# VESC6_4.net
KiCad netlist of a schematic drawn in Altium Designer
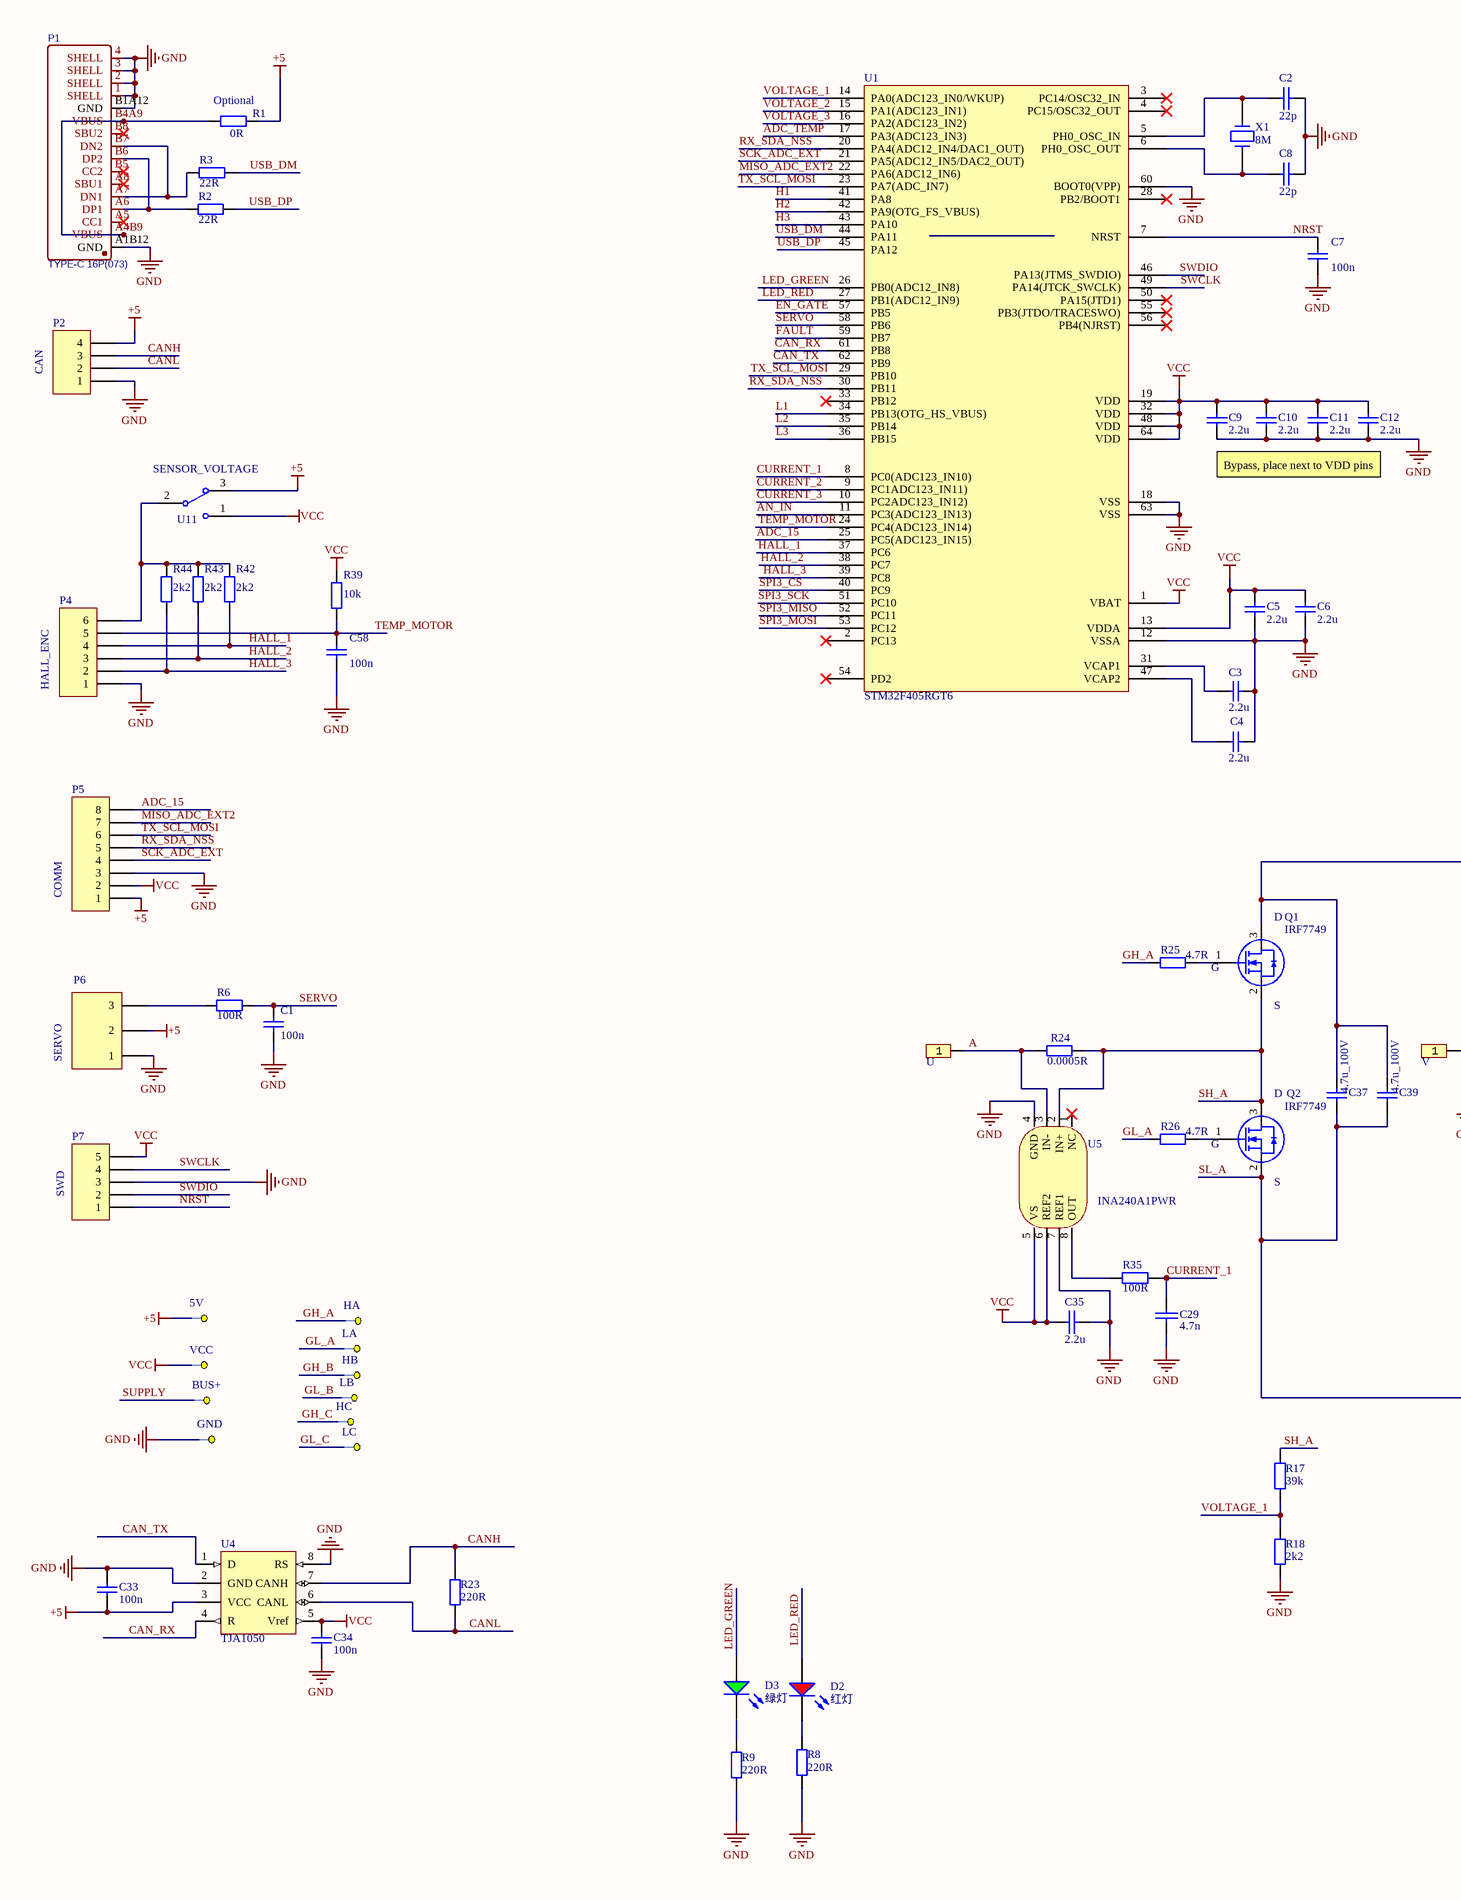
[diagram p0: VESC6.4.SchDoc, left]
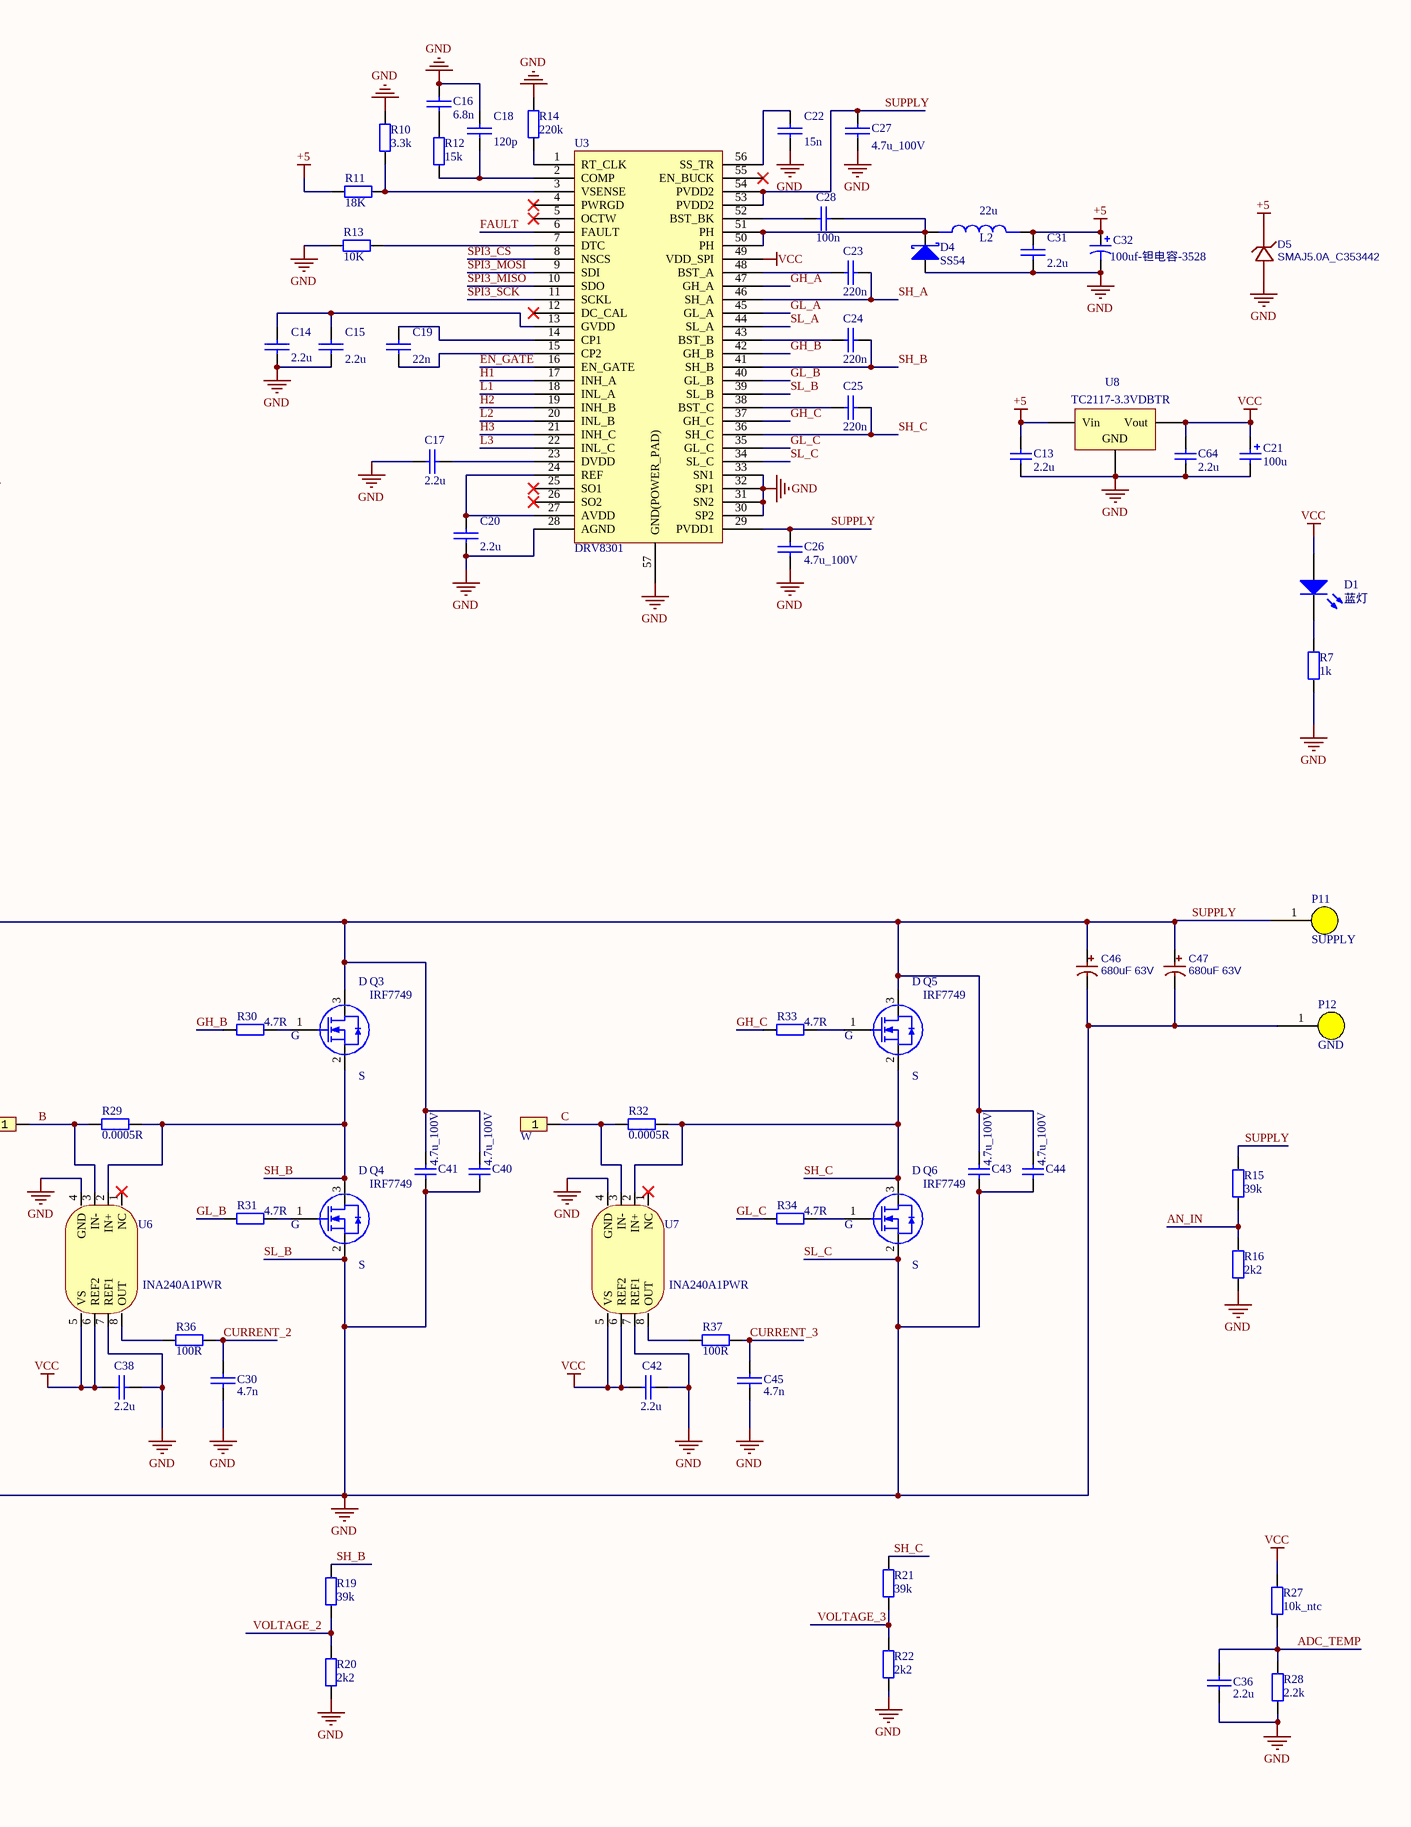
[diagram p1: VESC6.4.SchDoc, right]

(export (version "E")
  (design (tool "Eeschema 10.0.6"))
  (components
    (comp (ref "5V")
      (value "TEST")
      (footprint "TEST_2mm")
      (description "测试点")
      (libsource (lib "其它") (part "TEST"))
    )
    (comp (ref "BUS+")
      (value "TEST")
      (footprint "TEST_2mm")
      (description "测试点")
      (libsource (lib "其它") (part "TEST"))
    )
    (comp (ref "C1")
      (value "100n")
      (footprint "0603_C")
      (description "贴片电容")
      (libsource (lib "VESC_6") (part "0603 100nF (104) 10% 50V"))
    )
    (comp (ref "C2")
      (value "22p")
      (footprint "0603_C")
      (description "贴片电容")
      (libsource (lib "MY SCH LIB") (part "CAP"))
    )
    (comp (ref "C3")
      (value "2.2u")
      (footprint "0603_C")
      (description "贴片电容")
      (libsource (lib "VESC_6") (part "0603 2.2uF (225) 10% 16V"))
    )
    (comp (ref "C4")
      (value "2.2u")
      (footprint "0603_C")
      (description "贴片电容")
      (libsource (lib "VESC_6") (part "0603 2.2uF (225) 10% 16V"))
    )
    (comp (ref "C5")
      (value "2.2u")
      (footprint "0603_C")
      (description "贴片电容")
      (libsource (lib "VESC_6") (part "0603 2.2uF (225) 10% 16V"))
    )
    (comp (ref "C6")
      (value "2.2u")
      (footprint "0603_C")
      (description "贴片电容")
      (libsource (lib "VESC_6") (part "0603 2.2uF (225) 10% 16V"))
    )
    (comp (ref "C7")
      (value "100n")
      (footprint "0603_C")
      (description "贴片电容")
      (libsource (lib "VESC_6") (part "0603 100nF (104) 10% 50V"))
    )
    (comp (ref "C8")
      (value "22p")
      (footprint "0603_C")
      (description "贴片电容")
      (libsource (lib "MY SCH LIB") (part "CAP"))
    )
    (comp (ref "C9")
      (value "2.2u")
      (footprint "0603_C")
      (description "贴片电容")
      (libsource (lib "VESC_6") (part "0603 2.2uF (225) 10% 16V"))
    )
    (comp (ref "C10")
      (value "2.2u")
      (footprint "0603_C")
      (description "贴片电容")
      (libsource (lib "VESC_6") (part "0603 2.2uF (225) 10% 16V"))
    )
    (comp (ref "C11")
      (value "2.2u")
      (footprint "0603_C")
      (description "贴片电容")
      (libsource (lib "VESC_6") (part "0603 2.2uF (225) 10% 16V"))
    )
    (comp (ref "C12")
      (value "2.2u")
      (footprint "0603_C")
      (description "贴片电容")
      (libsource (lib "VESC_6") (part "0603 2.2uF (225) 10% 16V"))
    )
    (comp (ref "C13")
      (value "2.2u")
      (footprint "0603_C")
      (description "贴片电容")
      (libsource (lib "Miscellaneous Devices LC") (part "0603 2.2uF (225) 10% 16V"))
    )
    (comp (ref "C14") (value "2.2u") (footprint "0603_C") (libsource (lib "MY SCH LIB__JCH") (part "CAP")))
    (comp (ref "C15") (value "2.2u") (footprint "0603_C") (libsource (lib "MY SCH LIB__JCH") (part "CAP")))
    (comp (ref "C16") (value "6.8n") (footprint "0603_C") (libsource (lib "MY SCH LIB__JCH") (part "CAP")))
    (comp (ref "C17") (value "2.2u") (footprint "0603_C") (libsource (lib "MY SCH LIB__JCH") (part "CAP")))
    (comp (ref "C18") (value "120p") (footprint "0603_C") (libsource (lib "MY SCH LIB__JCH") (part "CAP")))
    (comp (ref "C19") (value "22n") (footprint "0603_C") (libsource (lib "MY SCH LIB__JCH") (part "CAP")))
    (comp (ref "C20") (value "2.2u") (footprint "0603_C") (libsource (lib "MY SCH LIB__JCH") (part "CAP")))
    (comp (ref "C21")
      (value "100u")
      (footprint "CASE-A_3216")
      (description "钽电容")
      (libsource (lib "Miscellaneous Devices LC") (part "3528 100uF (107) 10% 6.3V"))
    )
    (comp (ref "C22") (value "15n") (footprint "0603_C") (libsource (lib "MY SCH LIB__JCH") (part "CAP")))
    (comp (ref "C23") (value "220n") (footprint "0603_C") (libsource (lib "MY SCH LIB__JCH") (part "CAP")))
    (comp (ref "C24") (value "220n") (footprint "0603_C") (libsource (lib "MY SCH LIB__JCH") (part "CAP")))
    (comp (ref "C25") (value "220n") (footprint "0603_C") (libsource (lib "MY SCH LIB__JCH") (part "CAP")))
    (comp (ref "C26")
      (value "4.7u_100V")
      (footprint "1206_C")
      (libsource (lib "MY SCH LIB__JCH") (part "CAP"))
    )
    (comp (ref "C27")
      (value "4.7u_100V")
      (footprint "1206_C")
      (libsource (lib "MY SCH LIB__JCH") (part "CAP"))
    )
    (comp (ref "C28") (value "100n") (footprint "0603_C") (libsource (lib "MY SCH LIB__JCH") (part "CAP")))
    (comp (ref "C29") (value "4.7n") (footprint "0603_C") (libsource (lib "MY SCH LIB__JCH") (part "CAP")))
    (comp (ref "C30") (value "4.7n") (footprint "0603_C") (libsource (lib "MY SCH LIB__JCH") (part "CAP")))
    (comp (ref "C31") (value "2.2u") (footprint "0603_C") (libsource (lib "MY SCH LIB__JCH") (part "CAP")))
    (comp (ref "C32")
      (value "100uf-钽电容-3528")
      (footprint "CAP-SMD_L3.5-W2.8-R-RD")
      (libsource (lib "FOC") (part "CAP_HER"))
    )
    (comp (ref "C33")
      (value "100n")
      (footprint "0603_C")
      (description "Capacitor")
      (fields (field (name "PUBLISHER") "Altium Limited"))
      (libsource (lib "My Footprint") (part "CAP"))
    )
    (comp (ref "C34")
      (value "100n")
      (footprint "0603_C")
      (description "贴片电容")
      (fields (field (name "PUBLISHER") "Altium Limited"))
      (libsource (lib "My Footprint") (part "CAP"))
    )
    (comp (ref "C35") (value "2.2u") (footprint "0603_C") (libsource (lib "MY SCH LIB__JCH") (part "CAP")))
    (comp (ref "C36") (value "2.2u") (footprint "0603_C") (libsource (lib "MY SCH LIB__JCH") (part "CAP")))
    (comp (ref "C37")
      (value "4.7u_100V")
      (footprint "1206_C")
      (description "无极性电容")
      (fields (field (name "PUBLISHER") "Altium Limited"))
      (libsource (lib "Panel_Point") (part "Cap_6"))
    )
    (comp (ref "C38") (value "2.2u") (footprint "0603_C") (libsource (lib "MY SCH LIB__JCH") (part "CAP")))
    (comp (ref "C39")
      (value "4.7u_100V")
      (footprint "1206_C")
      (description "无极性电容")
      (fields (field (name "PUBLISHER") "Altium Limited"))
      (libsource (lib "Panel_Point") (part "Cap_6"))
    )
    (comp (ref "C40")
      (value "4.7u_100V")
      (footprint "1206_C")
      (description "无极性电容")
      (fields (field (name "PUBLISHER") "Altium Limited"))
      (libsource (lib "Panel_Point") (part "Cap_6"))
    )
    (comp (ref "C41")
      (value "4.7u_100V")
      (footprint "1206_C")
      (description "无极性电容")
      (fields (field (name "PUBLISHER") "Altium Limited"))
      (libsource (lib "Panel_Point") (part "Cap_6"))
    )
    (comp (ref "C42") (value "2.2u") (footprint "0603_C") (libsource (lib "MY SCH LIB__JCH") (part "CAP")))
    (comp (ref "C43")
      (value "4.7u_100V")
      (footprint "1206_C")
      (description "无极性电容")
      (fields (field (name "PUBLISHER") "Altium Limited"))
      (libsource (lib "Panel_Point") (part "Cap_6"))
    )
    (comp (ref "C44")
      (value "4.7u_100V")
      (footprint "1206_C")
      (description "无极性电容")
      (fields (field (name "PUBLISHER") "Altium Limited"))
      (libsource (lib "Panel_Point") (part "Cap_6"))
    )
    (comp (ref "C45") (value "4.7n") (footprint "0603_C") (libsource (lib "MY SCH LIB__JCH") (part "CAP")))
    (comp (ref "C46")
      (value "680uF 63V")
      (footprint "CAP-TH_BD12.5-P5.00-D1.2-FD")
      (fields
        (field (name "BOM_MANUFACTURER PART") "ERR1JM681W25OT")
        (field (name "BOM_SUPPLIER PART") "C106632")
      )
      (libsource (lib "altium-import") (part "root_3_680uF_"))
    )
    (comp (ref "C47")
      (value "680uF 63V")
      (footprint "CAP-TH_BD12.5-P5.00-D1.2-FD")
      (fields
        (field (name "BOM_MANUFACTURER PART") "ERR1JM681W25OT")
        (field (name "BOM_SUPPLIER PART") "C106632")
      )
      (libsource (lib "altium-import") (part "root_3_680uF_"))
    )
    (comp (ref "C58")
      (value "100n")
      (footprint "0603_C")
      (description "贴片电容")
      (libsource (lib "VESC_6") (part "0603 100nF (104) 10% 50V"))
    )
    (comp (ref "C64")
      (value "2.2u")
      (footprint "0603_C")
      (description "贴片电容")
      (libsource (lib "Cap") (part "0603 2.2uF (225) 10% 16V"))
    )
    (comp (ref "D1")
      (value "蓝灯")
      (footprint "0603_LED_S1")
      (description "发光二极管")
      (libsource (lib "Miscellaneous Devices LC") (part "0603 蓝灯"))
    )
    (comp (ref "D2")
      (value "红灯")
      (footprint "0603_LED_S1")
      (description "发光二极管")
      (libsource (lib "Miscellaneous Devices LC") (part "0603 红灯"))
    )
    (comp (ref "D3")
      (value "绿灯")
      (footprint "0603_LED_S1")
      (description "发光二极管")
      (libsource (lib "Miscellaneous Devices LC") (part "0603 绿灯"))
    )
    (comp (ref "D4")
      (value "SS54")
      (footprint "DIODE_3*5.3")
      (description "Schottky Diode")
      (fields (field (name "PUBLISHER") "Altium Limited"))
      (libsource (lib "FOC") (part "D Schottky"))
    )
    (comp (ref "D5")
      (value "SMAJ5.0A_C353442")
      (footprint "SMA_L4.4-W2.8-LS5.4-RD")
      (fields
        (field (name "BOM_SUPPLIER PART") "C353442")
        (field (name "BOM_MANUFACTURER PART") "SMAJ5.0A")
        (field (name "CONTRIBUTOR") "LCSC")
      )
      (libsource (lib "altium-import") (part "root_3_SMAJ5.0A_C353442_"))
    )
    (comp (ref "GND")
      (value "TEST")
      (footprint "TEST_2mm")
      (description "测试点")
      (libsource (lib "其它") (part "TEST"))
    )
    (comp (ref "HA")
      (value "TEST")
      (footprint "TEST_2mm")
      (description "测试点")
      (libsource (lib "其它") (part "TEST"))
    )
    (comp (ref "HB")
      (value "TEST")
      (footprint "TEST_2mm")
      (description "测试点")
      (libsource (lib "其它") (part "TEST"))
    )
    (comp (ref "HC")
      (value "TEST")
      (footprint "TEST_2mm")
      (description "测试点")
      (libsource (lib "其它") (part "TEST"))
    )
    (comp (ref "L2")
      (value "22u")
      (footprint "IND-SMD_L5.0-W5.0")
      (libsource (lib "Panel_Point") (part "IND"))
    )
    (comp (ref "LA")
      (value "TEST")
      (footprint "TEST_2mm")
      (description "测试点")
      (libsource (lib "其它") (part "TEST"))
    )
    (comp (ref "LB")
      (value "TEST")
      (footprint "TEST_2mm")
      (description "测试点")
      (libsource (lib "其它") (part "TEST"))
    )
    (comp (ref "LC")
      (value "TEST")
      (footprint "TEST_2mm")
      (description "测试点")
      (libsource (lib "其它") (part "TEST"))
    )
    (comp (ref "P1")
      (value "TYPE-C 16P(073)")
      (footprint "USB-C-SMD_16P - duplicate2")
      (fields (field (name "BOM_SUPPLIER PART") "C668624") (field (name "CONTRIBUTOR") "LCSC"))
      (libsource (lib "FOC") (part "TYPE-C 16P(073)_1"))
    )
    (comp (ref "P2")
      (value "CAN")
      (footprint "CONN-SMD_4P-P1.25_GH1.25-4PLI")
      (description "Header, 4-Pin")
      (fields (field (name "PUBLISHER") "Altium Limited"))
      (libsource (lib "FOC") (part "Header 4"))
    )
    (comp (ref "P4")
      (value "HALL_ENC")
      (footprint "CONN-SMD_6P-P1.25_WAFER-GH1.25-6PLB")
      (description "Header, 6-Pin")
      (fields (field (name "PUBLISHER") "Altium Limited"))
      (libsource (lib "FOC") (part "Header 6"))
    )
    (comp (ref "P5")
      (value "COMM")
      (footprint "CONN-SMD_8P-P1.25_WAFER-GH1.25-8PLB")
      (description "Header, 8-Pin")
      (fields (field (name "PUBLISHER") "Altium Limited"))
      (libsource (lib "Miscellaneous Connectors") (part "Header 8"))
    )
    (comp (ref "P6")
      (value "SERVO")
      (footprint "CONN-SMD_3P-P1.25_XUNPU_WAFER-GH1.25-3PLB")
      (description "接插件")
      (fields (field (name "PUBLISHER") "Altium Limited"))
      (libsource (lib "FOC") (part "Header 3"))
    )
    (comp (ref "P7")
      (value "SWD")
      (footprint "CONN-SMD_5P-P1.25_XUNPU_WAFER-GH1.25-5PLB")
      (description "Header, 5-Pin")
      (fields (field (name "PUBLISHER") "Altium Limited"))
      (libsource (lib "FOC") (part "Header 5"))
    )
    (comp (ref "P11") (value "SUPPLY") (footprint "Power Pad 6x6mm") (libsource (lib "JESC") (part "PadS")))
    (comp (ref "P12") (value "GND") (footprint "Power Pad 6x6mm") (libsource (lib "JESC") (part "PadS_1")))
    (comp (ref "Q1")
      (value "IRF7749")
      (footprint "DIRECTFET_L9.1-W7.0_IRF7759L2TRPBF")
      (description "MOS(场效应管)")
      (libsource (lib "FOC") (part "IRF7749"))
    )
    (comp (ref "Q2")
      (value "IRF7749")
      (footprint "DIRECTFET_L9.1-W7.0_IRF7759L2TRPBF")
      (description "MOS(场效应管)")
      (libsource (lib "FOC") (part "IRF7749"))
    )
    (comp (ref "Q3")
      (value "IRF7749")
      (footprint "DIRECTFET_L9.1-W7.0_IRF7759L2TRPBF")
      (description "MOS(场效应管)")
      (libsource (lib "FOC") (part "IRF7749"))
    )
    (comp (ref "Q4")
      (value "IRF7749")
      (footprint "DIRECTFET_L9.1-W7.0_IRF7759L2TRPBF")
      (description "MOS(场效应管)")
      (libsource (lib "FOC") (part "IRF7749"))
    )
    (comp (ref "Q5")
      (value "IRF7749")
      (footprint "DIRECTFET_L9.1-W7.0_IRF7759L2TRPBF")
      (description "MOS(场效应管)")
      (libsource (lib "FOC") (part "IRF7749"))
    )
    (comp (ref "Q6")
      (value "IRF7749")
      (footprint "DIRECTFET_L9.1-W7.0_IRF7759L2TRPBF")
      (description "MOS(场效应管)")
      (libsource (lib "FOC") (part "IRF7749"))
    )
    (comp (ref "R1")
      (value "0R")
      (footprint "0603_R")
      (description "Resistor")
      (fields (field (name "PUBLISHER") "Altium Limited"))
      (libsource (lib "") (part "Res2_1"))
    )
    (comp (ref "R2")
      (value "22R")
      (footprint "0603_R")
      (description "Resistor")
      (fields (field (name "PUBLISHER") "Altium Limited"))
      (libsource (lib "") (part "Res2_1"))
    )
    (comp (ref "R3")
      (value "22R")
      (footprint "0603_R")
      (description "Resistor")
      (fields (field (name "PUBLISHER") "Altium Limited"))
      (libsource (lib "") (part "Res2_1"))
    )
    (comp (ref "R6")
      (value "100R")
      (footprint "0603_R")
      (description "Resistor")
      (fields (field (name "PUBLISHER") "Altium Limited"))
      (libsource (lib "") (part "Res2_1"))
    )
    (comp (ref "R7")
      (value "1k")
      (footprint "0603_R")
      (description "Resistor")
      (fields (field (name "PUBLISHER") "Altium Limited"))
      (libsource (lib "") (part "Res2_3"))
    )
    (comp (ref "R8")
      (value "220R")
      (footprint "0603_R")
      (description "Resistor")
      (fields (field (name "PUBLISHER") "Altium Limited"))
      (libsource (lib "") (part "Res2_3"))
    )
    (comp (ref "R9")
      (value "220R")
      (footprint "0603_R")
      (description "Resistor")
      (fields (field (name "PUBLISHER") "Altium Limited"))
      (libsource (lib "") (part "Res2_3"))
    )
    (comp (ref "R10")
      (value "3.3k")
      (footprint "0603_R")
      (description "Resistor")
      (fields (field (name "PUBLISHER") "Altium Limited"))
      (libsource (lib "") (part "Res2_3"))
    )
    (comp (ref "R11")
      (value "18K")
      (footprint "0603_R")
      (description "Resistor")
      (fields (field (name "PUBLISHER") "Altium Limited"))
      (libsource (lib "") (part "Res2_2"))
    )
    (comp (ref "R12")
      (value "15k")
      (footprint "0603_R")
      (description "Resistor")
      (fields (field (name "PUBLISHER") "Altium Limited"))
      (libsource (lib "") (part "Res2_3"))
    )
    (comp (ref "R13")
      (value "10K")
      (footprint "0603_R")
      (description "Resistor")
      (fields (field (name "PUBLISHER") "Altium Limited"))
      (libsource (lib "") (part "Res2_2"))
    )
    (comp (ref "R14")
      (value "220k")
      (footprint "0603_R")
      (description "Resistor")
      (fields (field (name "PUBLISHER") "Altium Limited"))
      (libsource (lib "") (part "Res2_3"))
    )
    (comp (ref "R15")
      (value "39k")
      (footprint "0603_R")
      (description "Resistor")
      (fields (field (name "PUBLISHER") "Altium Limited"))
      (libsource (lib "") (part "Res2_3"))
    )
    (comp (ref "R16")
      (value "2k2")
      (footprint "0603_R")
      (description "Resistor")
      (fields (field (name "PUBLISHER") "Altium Limited"))
      (libsource (lib "Miscellaneous Devices") (part "Res2"))
    )
    (comp (ref "R17")
      (value "39k")
      (footprint "0603_R")
      (description "Resistor")
      (fields (field (name "PUBLISHER") "Altium Limited"))
      (libsource (lib "") (part "Res2_3"))
    )
    (comp (ref "R18")
      (value "2k2")
      (footprint "0603_R")
      (description "Resistor")
      (fields (field (name "PUBLISHER") "Altium Limited"))
      (libsource (lib "Miscellaneous Devices") (part "Res2"))
    )
    (comp (ref "R19")
      (value "39k")
      (footprint "0603_R")
      (description "Resistor")
      (fields (field (name "PUBLISHER") "Altium Limited"))
      (libsource (lib "") (part "Res2_3"))
    )
    (comp (ref "R20")
      (value "2k2")
      (footprint "0603_R")
      (description "Resistor")
      (fields (field (name "PUBLISHER") "Altium Limited"))
      (libsource (lib "Miscellaneous Devices") (part "Res2"))
    )
    (comp (ref "R21")
      (value "39k")
      (footprint "0603_R")
      (description "Resistor")
      (fields (field (name "PUBLISHER") "Altium Limited"))
      (libsource (lib "") (part "Res2_3"))
    )
    (comp (ref "R22")
      (value "2k2")
      (footprint "0603_R")
      (description "Resistor")
      (fields (field (name "PUBLISHER") "Altium Limited"))
      (libsource (lib "Miscellaneous Devices") (part "Res2"))
    )
    (comp (ref "R23")
      (value "220R")
      (footprint "0603_R")
      (description "贴片电阻")
      (fields (field (name "Comment") "Res1") (field (name "PUBLISHER") "Altium Limited"))
      (libsource (lib "") (part "Res1_2"))
    )
    (comp (ref "R24")
      (value "0.0005R")
      (footprint "R3920")
      (description "贴片电阻")
      (fields (field (name "Comment") "Res1") (field (name "PUBLISHER") "Altium Limited"))
      (libsource (lib "SMC_Devices") (part "Res1"))
    )
    (comp (ref "R25")
      (value "4.7R")
      (footprint "0603_R")
      (description "贴片电阻")
      (fields (field (name "Comment") "Res1") (field (name "PUBLISHER") "Altium Limited"))
      (libsource (lib "") (part "Res1_1"))
    )
    (comp (ref "R26")
      (value "4.7R")
      (footprint "0603_R")
      (description "贴片电阻")
      (fields (field (name "Comment") "Res1") (field (name "PUBLISHER") "Altium Limited"))
      (libsource (lib "") (part "Res1_1"))
    )
    (comp (ref "R27")
      (value "10k_ntc")
      (footprint "0603_R")
      (description "Resistor")
      (fields (field (name "PUBLISHER") "Altium Limited"))
      (libsource (lib "") (part "Res2_3"))
    )
    (comp (ref "R28")
      (value "2.2k")
      (footprint "0603_R")
      (description "Resistor")
      (fields (field (name "PUBLISHER") "Altium Limited"))
      (libsource (lib "Miscellaneous Devices") (part "Res2"))
    )
    (comp (ref "R29")
      (value "0.0005R")
      (footprint "R3920")
      (description "贴片电阻")
      (fields (field (name "Comment") "Res1") (field (name "PUBLISHER") "Altium Limited"))
      (libsource (lib "SMC_Devices") (part "Res1"))
    )
    (comp (ref "R30")
      (value "4.7R")
      (footprint "0603_R")
      (description "贴片电阻")
      (fields (field (name "Comment") "Res1") (field (name "PUBLISHER") "Altium Limited"))
      (libsource (lib "") (part "Res1_1"))
    )
    (comp (ref "R31")
      (value "4.7R")
      (footprint "0603_R")
      (description "贴片电阻")
      (fields (field (name "Comment") "Res1") (field (name "PUBLISHER") "Altium Limited"))
      (libsource (lib "") (part "Res1_1"))
    )
    (comp (ref "R32")
      (value "0.0005R")
      (footprint "R3920")
      (description "贴片电阻")
      (fields (field (name "Comment") "Res1") (field (name "PUBLISHER") "Altium Limited"))
      (libsource (lib "SMC_Devices") (part "Res1"))
    )
    (comp (ref "R33")
      (value "4.7R")
      (footprint "0603_R")
      (description "贴片电阻")
      (fields (field (name "Comment") "Res1") (field (name "PUBLISHER") "Altium Limited"))
      (libsource (lib "") (part "Res1_1"))
    )
    (comp (ref "R34")
      (value "4.7R")
      (footprint "0603_R")
      (description "贴片电阻")
      (fields (field (name "Comment") "Res1") (field (name "PUBLISHER") "Altium Limited"))
      (libsource (lib "") (part "Res1_1"))
    )
    (comp (ref "R35")
      (value "100R")
      (footprint "0603_R")
      (description "Resistor")
      (fields (field (name "PUBLISHER") "Altium Limited"))
      (libsource (lib "") (part "Res2_1"))
    )
    (comp (ref "R36")
      (value "100R")
      (footprint "0603_R")
      (description "Resistor")
      (fields (field (name "PUBLISHER") "Altium Limited"))
      (libsource (lib "") (part "Res2_1"))
    )
    (comp (ref "R37")
      (value "100R")
      (footprint "0603_R")
      (description "Resistor")
      (fields (field (name "PUBLISHER") "Altium Limited"))
      (libsource (lib "") (part "Res2_1"))
    )
    (comp (ref "R39")
      (value "10k")
      (footprint "0603_R")
      (description "Resistor")
      (fields (field (name "PUBLISHER") "Altium Limited"))
      (libsource (lib "Miscellaneous Devices") (part "Res2"))
    )
    (comp (ref "R42")
      (value "2k2")
      (footprint "0603_R")
      (description "Resistor")
      (fields (field (name "PUBLISHER") "Altium Limited"))
      (libsource (lib "Miscellaneous Devices") (part "Res2"))
    )
    (comp (ref "R43")
      (value "2k2")
      (footprint "0603_R")
      (description "Resistor")
      (fields (field (name "PUBLISHER") "Altium Limited"))
      (libsource (lib "Miscellaneous Devices") (part "Res2"))
    )
    (comp (ref "R44")
      (value "2k2")
      (footprint "0603_R")
      (description "Resistor")
      (fields (field (name "PUBLISHER") "Altium Limited"))
      (libsource (lib "Miscellaneous Devices") (part "Res2"))
    )
    (comp (ref "U")
      (value "HDR-PAD")
      (footprint "MOTOR_PAD")
      (description "Header")
      (libsource (lib "Integrated_Library") (part "HDR-PAD_2.54"))
    )
    (comp (ref "U1")
      (value "STM32F405RGT6")
      (footprint "LQFP-64_10x10x05P")
      (libsource (lib "VESC6 V1.0") (part "STM32F405RGT6"))
    )
    (comp (ref "U3")
      (value "DRV8301")
      (footprint "DRV8301")
      (description "预驱")
      (libsource (lib "FOC") (part "DRV8301"))
    )
    (comp (ref "U4")
      (value "TJA1050")
      (footprint "TJA1050")
      (libsource (lib "My Footprint") (part "TJA1050"))
    )
    (comp (ref "U5")
      (value "INA240A1PWR")
      (footprint "TSSOP-8_L4.4-W3.0-P0.65-LS6.4-BL")
      (description "INA240 电压输出、高/低侧测量、双向零漂移系列")
      (fields (field (name "MANUFACTURER") "TI(德州仪器)"))
      (libsource (lib "Transistor") (part "INA240A1PWR"))
    )
    (comp (ref "U6")
      (value "INA240A1PWR")
      (footprint "TSSOP-8_L4.4-W3.0-P0.65-LS6.4-BL")
      (description "INA240 电压输出、高/低侧测量、双向零漂移系列")
      (fields (field (name "MANUFACTURER") "TI(德州仪器)"))
      (libsource (lib "Transistor") (part "INA240A1PWR"))
    )
    (comp (ref "U7")
      (value "INA240A1PWR")
      (footprint "TSSOP-8_L4.4-W3.0-P0.65-LS6.4-BL")
      (description "INA240 电压输出、高/低侧测量、双向零漂移系列")
      (fields (field (name "MANUFACTURER") "TI(德州仪器)"))
      (libsource (lib "Transistor") (part "INA240A1PWR"))
    )
    (comp (ref "U8")
      (value "TC2117-3.3VDBTR")
      (footprint "SOT-223")
      (description "低压差线性稳压(LDO)")
      (libsource (lib "LDO") (part "SOT-223 AMS1117-3.3"))
    )
    (comp (ref "U11")
      (value "MSK-12C01-07")
      (footprint "MSK-12C01-07")
      (libsource (lib "VESC_6") (part "MSK-12C01-07"))
    )
    (comp (ref "V")
      (value "HDR-PAD")
      (footprint "MOTOR_PAD")
      (description "Header")
      (libsource (lib "Integrated_Library") (part "HDR-PAD_2.54"))
    )
    (comp (ref "VCC")
      (value "TEST")
      (footprint "TEST_2mm")
      (description "测试点")
      (libsource (lib "其它") (part "TEST"))
    )
    (comp (ref "W")
      (value "HDR-PAD")
      (footprint "MOTOR_PAD")
      (description "Header")
      (libsource (lib "Integrated_Library") (part "HDR-PAD_2.54"))
    )
    (comp (ref "X1")
      (value "8M")
      (footprint "晶振")
      (description "XTAL_SMD5032 Crystal")
      (libsource (lib "MY SCH LIB") (part "CRYSTAL"))
    )
  )
  (nets
    (net (code "1") (name "+5") (class "Default")
      (node (ref "5V") (pin "1") (pinfunction "1_1") (pintype "passive"))
      (node (ref "C13") (pin "2") (pinfunction "2_2") (pintype "passive"))
      (node (ref "C31") (pin "2") (pinfunction "2_2") (pintype "passive"))
      (node (ref "C32") (pin "1") (pinfunction "1_1") (pintype "passive"))
      (node (ref "C33") (pin "1") (pinfunction "1_1") (pintype "passive"))
      (node (ref "D5") (pin "1") (pinfunction "C_1") (pintype "passive"))
      (node (ref "L2") (pin "2") (pinfunction "Pri-_2") (pintype "passive"))
      (node (ref "P2") (pin "4") (pinfunction "4_4") (pintype "passive"))
      (node (ref "P5") (pin "1") (pinfunction "1_1") (pintype "passive"))
      (node (ref "P6") (pin "2") (pinfunction "2_2") (pintype "passive"))
      (node (ref "R1") (pin "1") (pinfunction "1_1") (pintype "passive"))
      (node (ref "R11") (pin "1") (pinfunction "1_1") (pintype "passive"))
      (node (ref "U11") (pin "3") (pinfunction "3_3") (pintype "passive"))
      (node (ref "U4") (pin "3") (pinfunction "VCC_3") (pintype "passive"))
      (node (ref "U8") (pin "3") (pinfunction "Vin_3") (pintype "passive"))
    )
    (net (code "2") (name "/A") (class "Default")
      (node (ref "R24") (pin "2") (pinfunction "2_2") (pintype "passive"))
      (node (ref "U") (pin "1") (pinfunction "1_1") (pintype "passive"))
      (node (ref "U5") (pin "3") (pinfunction "IN-_3") (pintype "passive"))
    )
    (net (code "3") (name "/ADC_15") (class "Default")
      (node (ref "P5") (pin "8") (pinfunction "8_8") (pintype "passive"))
      (node (ref "U1") (pin "25") (pinfunction "PC5(ADC123_IN15)_25") (pintype "passive"))
    )
    (net (code "4") (name "/ADC_TEMP") (class "Default")
      (node (ref "C36") (pin "1") (pinfunction "1_1") (pintype "passive"))
      (node (ref "R27") (pin "1") (pinfunction "1_1") (pintype "passive"))
      (node (ref "R28") (pin "1") (pinfunction "1_1") (pintype "passive"))
      (node (ref "U1") (pin "17") (pinfunction "PA3(ADC123_IN3)_17") (pintype "passive"))
    )
    (net (code "5") (name "/AN_IN") (class "Default")
      (node (ref "R15") (pin "1") (pinfunction "1_1") (pintype "passive"))
      (node (ref "R16") (pin "1") (pinfunction "1_1") (pintype "passive"))
      (node (ref "U1") (pin "11") (pinfunction "PC3(ADC123_IN13)_11") (pintype "passive"))
    )
    (net (code "6") (name "/B") (class "Default")
      (node (ref "R29") (pin "2") (pinfunction "2_2") (pintype "passive"))
      (node (ref "U6") (pin "3") (pinfunction "IN-_3") (pintype "passive"))
      (node (ref "V") (pin "1") (pinfunction "1_1") (pintype "passive"))
    )
    (net (code "7") (name "/C") (class "Default")
      (node (ref "R32") (pin "2") (pinfunction "2_2") (pintype "passive"))
      (node (ref "U7") (pin "3") (pinfunction "IN-_3") (pintype "passive"))
      (node (ref "W") (pin "1") (pinfunction "1_1") (pintype "passive"))
    )
    (net (code "8") (name "/CANH") (class "Default")
      (node (ref "P2") (pin "3") (pinfunction "3_3") (pintype "passive"))
      (node (ref "R23") (pin "2") (pinfunction "2_2") (pintype "passive"))
      (node (ref "U4") (pin "7") (pinfunction "CANH_7") (pintype "bidirectional"))
    )
    (net (code "9") (name "/CANL") (class "Default")
      (node (ref "P2") (pin "2") (pinfunction "2_2") (pintype "passive"))
      (node (ref "R23") (pin "1") (pinfunction "1_1") (pintype "passive"))
      (node (ref "U4") (pin "6") (pinfunction "CANL_6") (pintype "bidirectional"))
    )
    (net (code "10") (name "/CAN_RX") (class "Default")
      (node (ref "U1") (pin "61") (pinfunction "PB8_61") (pintype "passive"))
      (node (ref "U4") (pin "4") (pinfunction "R_4") (pintype "output"))
    )
    (net (code "11") (name "/CAN_TX") (class "Default")
      (node (ref "U1") (pin "62") (pinfunction "PB9_62") (pintype "passive"))
      (node (ref "U4") (pin "1") (pinfunction "D_1") (pintype "input"))
    )
    (net (code "12") (name "/CURRENT_1") (class "Default")
      (node (ref "C29") (pin "1") (pinfunction "1_1") (pintype "passive"))
      (node (ref "R35") (pin "1") (pinfunction "1_1") (pintype "passive"))
      (node (ref "U1") (pin "8") (pinfunction "PC0(ADC123_IN10)_8") (pintype "passive"))
    )
    (net (code "13") (name "/CURRENT_2") (class "Default")
      (node (ref "C30") (pin "1") (pinfunction "1_1") (pintype "passive"))
      (node (ref "R36") (pin "1") (pinfunction "1_1") (pintype "passive"))
      (node (ref "U1") (pin "9") (pinfunction "PC1ADC123_IN11)_9") (pintype "passive"))
    )
    (net (code "14") (name "/CURRENT_3") (class "Default")
      (node (ref "C45") (pin "1") (pinfunction "1_1") (pintype "passive"))
      (node (ref "R37") (pin "1") (pinfunction "1_1") (pintype "passive"))
      (node (ref "U1") (pin "10") (pinfunction "PC2ADC123_IN12)_10") (pintype "passive"))
    )
    (net (code "15") (name "/EN_GATE") (class "Default")
      (node (ref "U1") (pin "57") (pinfunction "PB5_57") (pintype "passive"))
      (node (ref "U3") (pin "16") (pinfunction "EN_GATE_16") (pintype "passive"))
    )
    (net (code "16") (name "/FAULT") (class "Default")
      (node (ref "U1") (pin "59") (pinfunction "PB7_59") (pintype "passive"))
      (node (ref "U3") (pin "6") (pinfunction "FAULT_6") (pintype "passive"))
    )
    (net (code "17") (name "/GH_A") (class "Default")
      (node (ref "HA") (pin "1") (pinfunction "1_1") (pintype "passive"))
      (node (ref "R25") (pin "1") (pinfunction "1_1") (pintype "passive"))
      (node (ref "U3") (pin "47") (pinfunction "GH_A_47") (pintype "passive"))
    )
    (net (code "18") (name "/GH_B") (class "Default")
      (node (ref "HB") (pin "1") (pinfunction "1_1") (pintype "passive"))
      (node (ref "R30") (pin "1") (pinfunction "1_1") (pintype "passive"))
      (node (ref "U3") (pin "42") (pinfunction "GH_B_42") (pintype "passive"))
    )
    (net (code "19") (name "/GH_C") (class "Default")
      (node (ref "HC") (pin "1") (pinfunction "1_1") (pintype "passive"))
      (node (ref "R33") (pin "1") (pinfunction "1_1") (pintype "passive"))
      (node (ref "U3") (pin "37") (pinfunction "GH_C_37") (pintype "passive"))
    )
    (net (code "20") (name "/GL_A") (class "Default")
      (node (ref "LA") (pin "1") (pinfunction "1_1") (pintype "passive"))
      (node (ref "R26") (pin "1") (pinfunction "1_1") (pintype "passive"))
      (node (ref "U3") (pin "45") (pinfunction "GL_A_45") (pintype "passive"))
    )
    (net (code "21") (name "/GL_B") (class "Default")
      (node (ref "LB") (pin "1") (pinfunction "1_1") (pintype "passive"))
      (node (ref "R31") (pin "1") (pinfunction "1_1") (pintype "passive"))
      (node (ref "U3") (pin "40") (pinfunction "GL_B_40") (pintype "passive"))
    )
    (net (code "22") (name "/GL_C") (class "Default")
      (node (ref "LC") (pin "1") (pinfunction "1_1") (pintype "passive"))
      (node (ref "R34") (pin "1") (pinfunction "1_1") (pintype "passive"))
      (node (ref "U3") (pin "35") (pinfunction "GL_C_35") (pintype "passive"))
    )
    (net (code "23") (name "/H1") (class "Default")
      (node (ref "U1") (pin "41") (pinfunction "PA8_41") (pintype "passive"))
      (node (ref "U3") (pin "17") (pinfunction "INH_A_17") (pintype "passive"))
    )
    (net (code "24") (name "/H2") (class "Default")
      (node (ref "U1") (pin "42") (pinfunction "PA9(OTG_FS_VBUS)_42") (pintype "passive"))
      (node (ref "U3") (pin "19") (pinfunction "INH_B_19") (pintype "passive"))
    )
    (net (code "25") (name "/H3") (class "Default")
      (node (ref "U1") (pin "43") (pinfunction "PA10_43") (pintype "passive"))
      (node (ref "U3") (pin "21") (pinfunction "INH_C_21") (pintype "passive"))
    )
    (net (code "26") (name "/HALL_1") (class "Default")
      (node (ref "P4") (pin "4") (pinfunction "4_4") (pintype "passive"))
      (node (ref "R42") (pin "2") (pinfunction "2_2") (pintype "passive"))
      (node (ref "U1") (pin "37") (pinfunction "PC6_37") (pintype "passive"))
    )
    (net (code "27") (name "/HALL_2") (class "Default")
      (node (ref "P4") (pin "3") (pinfunction "3_3") (pintype "passive"))
      (node (ref "R43") (pin "2") (pinfunction "2_2") (pintype "passive"))
      (node (ref "U1") (pin "38") (pinfunction "PC7_38") (pintype "passive"))
    )
    (net (code "28") (name "/HALL_3") (class "Default")
      (node (ref "P4") (pin "2") (pinfunction "2_2") (pintype "passive"))
      (node (ref "R44") (pin "2") (pinfunction "2_2") (pintype "passive"))
      (node (ref "U1") (pin "39") (pinfunction "PC8_39") (pintype "passive"))
    )
    (net (code "29") (name "/L1") (class "Default")
      (node (ref "U1") (pin "34") (pinfunction "PB13(OTG_HS_VBUS)_34") (pintype "passive"))
      (node (ref "U3") (pin "18") (pinfunction "INL_A_18") (pintype "passive"))
    )
    (net (code "30") (name "/L2") (class "Default")
      (node (ref "U1") (pin "35") (pinfunction "PB14_35") (pintype "passive"))
      (node (ref "U3") (pin "20") (pinfunction "INL_B_20") (pintype "passive"))
    )
    (net (code "31") (name "/L3") (class "Default")
      (node (ref "U1") (pin "36") (pinfunction "PB15_36") (pintype "passive"))
      (node (ref "U3") (pin "22") (pinfunction "INL_C_22") (pintype "passive"))
    )
    (net (code "32") (name "/LED_GREEN") (class "Default")
      (node (ref "D3") (pin "A") (pinfunction "A_A") (pintype "passive"))
      (node (ref "U1") (pin "26") (pinfunction "PB0(ADC12_IN8)_26") (pintype "passive"))
    )
    (net (code "33") (name "/LED_RED") (class "Default")
      (node (ref "D2") (pin "A") (pinfunction "A_A") (pintype "passive"))
      (node (ref "U1") (pin "27") (pinfunction "PB1(ADC12_IN9)_27") (pintype "passive"))
    )
    (net (code "34") (name "/MISO_ADC_EXT2") (class "Default")
      (node (ref "P5") (pin "7") (pinfunction "7_7") (pintype "passive"))
      (node (ref "U1") (pin "22") (pinfunction "PA6(ADC12_IN6)_22") (pintype "passive"))
    )
    (net (code "35") (name "/NRST") (class "Default")
      (node (ref "C7") (pin "2") (pinfunction "2_2") (pintype "passive"))
      (node (ref "P7") (pin "1") (pinfunction "1_1") (pintype "passive"))
      (node (ref "U1") (pin "7") (pinfunction "NRST_7") (pintype "passive"))
    )
    (net (code "36") (name "/RX_SDA_NSS") (class "Default")
      (node (ref "P5") (pin "5") (pinfunction "5_5") (pintype "passive"))
      (node (ref "U1") (pin "20") (pinfunction "PA4(ADC12_IN4/DAC1_OUT)_20") (pintype "passive"))
      (node (ref "U1") (pin "30") (pinfunction "PB11_30") (pintype "passive"))
    )
    (net (code "37") (name "/SCK_ADC_EXT") (class "Default")
      (node (ref "P5") (pin "4") (pinfunction "4_4") (pintype "passive"))
      (node (ref "U1") (pin "21") (pinfunction "PA5(ADC12_IN5/DAC2_OUT)_21") (pintype "passive"))
    )
    (net (code "38") (name "/SERVO") (class "Default")
      (node (ref "C1") (pin "2") (pinfunction "2_2") (pintype "passive"))
      (node (ref "R6") (pin "1") (pinfunction "1_1") (pintype "passive"))
      (node (ref "U1") (pin "58") (pinfunction "PB6_58") (pintype "passive"))
    )
    (net (code "39") (name "/SH_A") (class "Default")
      (node (ref "C23") (pin "1") (pinfunction "1_1") (pintype "passive"))
      (node (ref "Q1") (pin "2") (pinfunction "S_2") (pintype "passive"))
      (node (ref "Q2") (pin "3") (pinfunction "D_3") (pintype "passive"))
      (node (ref "R17") (pin "2") (pinfunction "2_2") (pintype "passive"))
      (node (ref "R24") (pin "1") (pinfunction "1_1") (pintype "passive"))
      (node (ref "U3") (pin "46") (pinfunction "SH_A_46") (pintype "passive"))
      (node (ref "U5") (pin "2") (pinfunction "IN+_2") (pintype "passive"))
    )
    (net (code "40") (name "/SH_B") (class "Default")
      (node (ref "C24") (pin "1") (pinfunction "1_1") (pintype "passive"))
      (node (ref "Q3") (pin "2") (pinfunction "S_2") (pintype "passive"))
      (node (ref "Q4") (pin "3") (pinfunction "D_3") (pintype "passive"))
      (node (ref "R19") (pin "2") (pinfunction "2_2") (pintype "passive"))
      (node (ref "R29") (pin "1") (pinfunction "1_1") (pintype "passive"))
      (node (ref "U3") (pin "41") (pinfunction "SH_B_41") (pintype "passive"))
      (node (ref "U6") (pin "2") (pinfunction "IN+_2") (pintype "passive"))
    )
    (net (code "41") (name "/SH_C") (class "Default")
      (node (ref "C25") (pin "1") (pinfunction "1_1") (pintype "passive"))
      (node (ref "Q5") (pin "2") (pinfunction "S_2") (pintype "passive"))
      (node (ref "Q6") (pin "3") (pinfunction "D_3") (pintype "passive"))
      (node (ref "R21") (pin "2") (pinfunction "2_2") (pintype "passive"))
      (node (ref "R32") (pin "1") (pinfunction "1_1") (pintype "passive"))
      (node (ref "U3") (pin "36") (pinfunction "SH_C_36") (pintype "passive"))
      (node (ref "U7") (pin "2") (pinfunction "IN+_2") (pintype "passive"))
    )
    (net (code "42") (name "/SPI3_CS") (class "Default")
      (node (ref "U1") (pin "40") (pinfunction "PC9_40") (pintype "passive"))
      (node (ref "U3") (pin "8") (pinfunction "NSCS_8") (pintype "passive"))
    )
    (net (code "43") (name "/SPI3_MISO") (class "Default")
      (node (ref "U1") (pin "52") (pinfunction "PC11_52") (pintype "passive"))
      (node (ref "U3") (pin "10") (pinfunction "SDO_10") (pintype "passive"))
    )
    (net (code "44") (name "/SPI3_MOSI") (class "Default")
      (node (ref "U1") (pin "53") (pinfunction "PC12_53") (pintype "passive"))
      (node (ref "U3") (pin "9") (pinfunction "SDI_9") (pintype "passive"))
    )
    (net (code "45") (name "/SPI3_SCK") (class "Default")
      (node (ref "U1") (pin "51") (pinfunction "PC10_51") (pintype "passive"))
      (node (ref "U3") (pin "11") (pinfunction "SCKL_11") (pintype "passive"))
    )
    (net (code "46") (name "/SUPPLY") (class "Default")
      (node (ref "BUS+") (pin "1") (pinfunction "1_1") (pintype "passive"))
      (node (ref "C26") (pin "2") (pinfunction "2_2") (pintype "passive"))
      (node (ref "C27") (pin "2") (pinfunction "2_2") (pintype "passive"))
      (node (ref "C37") (pin "2") (pinfunction "2_2") (pintype "passive"))
      (node (ref "C39") (pin "2") (pinfunction "2_2") (pintype "passive"))
      (node (ref "C40") (pin "2") (pinfunction "2_2") (pintype "passive"))
      (node (ref "C41") (pin "2") (pinfunction "2_2") (pintype "passive"))
      (node (ref "C43") (pin "2") (pinfunction "2_2") (pintype "passive"))
      (node (ref "C44") (pin "2") (pinfunction "2_2") (pintype "passive"))
      (node (ref "C46") (pin "1") (pinfunction "1_1") (pintype "passive"))
      (node (ref "C47") (pin "1") (pinfunction "1_1") (pintype "passive"))
      (node (ref "P11") (pin "1") (pinfunction "15_1") (pintype "passive"))
      (node (ref "Q1") (pin "3") (pinfunction "D_3") (pintype "passive"))
      (node (ref "Q3") (pin "3") (pinfunction "D_3") (pintype "passive"))
      (node (ref "Q5") (pin "3") (pinfunction "D_3") (pintype "passive"))
      (node (ref "R15") (pin "2") (pinfunction "2_2") (pintype "passive"))
      (node (ref "U3") (pin "29") (pinfunction "PVDD1_29") (pintype "passive"))
      (node (ref "U3") (pin "53") (pinfunction "PVDD2_53") (pintype "passive"))
      (node (ref "U3") (pin "54") (pinfunction "PVDD2_54") (pintype "passive"))
    )
    (net (code "47") (name "/SWCLK") (class "Default")
      (node (ref "P7") (pin "4") (pinfunction "4_4") (pintype "passive"))
      (node (ref "U1") (pin "49") (pinfunction "PA14(JTCK_SWCLK)_49") (pintype "passive"))
    )
    (net (code "48") (name "/SWDIO") (class "Default")
      (node (ref "P7") (pin "2") (pinfunction "2_2") (pintype "passive"))
      (node (ref "U1") (pin "46") (pinfunction "PA13(JTMS_SWDIO)_46") (pintype "passive"))
    )
    (net (code "49") (name "/TEMP_MOTOR") (class "Default")
      (node (ref "C58") (pin "2") (pinfunction "2_2") (pintype "passive"))
      (node (ref "P4") (pin "5") (pinfunction "5_5") (pintype "passive"))
      (node (ref "R39") (pin "2") (pinfunction "2_2") (pintype "passive"))
      (node (ref "U1") (pin "24") (pinfunction "PC4(ADC123_IN14)_24") (pintype "passive"))
    )
    (net (code "50") (name "/TX_SCL_MOSI") (class "Default")
      (node (ref "P5") (pin "6") (pinfunction "6_6") (pintype "passive"))
      (node (ref "U1") (pin "23") (pinfunction "PA7(ADC_IN7)_23") (pintype "passive"))
      (node (ref "U1") (pin "29") (pinfunction "PB10_29") (pintype "passive"))
    )
    (net (code "51") (name "/USB_DM") (class "Default")
      (node (ref "R3") (pin "1") (pinfunction "1_1") (pintype "passive"))
      (node (ref "U1") (pin "44") (pinfunction "PA11_44") (pintype "passive"))
    )
    (net (code "52") (name "/USB_DP") (class "Default")
      (node (ref "R2") (pin "1") (pinfunction "1_1") (pintype "passive"))
      (node (ref "U1") (pin "45") (pinfunction "PA12_45") (pintype "passive"))
    )
    (net (code "53") (name "/VOLTAGE_1") (class "Default")
      (node (ref "R17") (pin "1") (pinfunction "1_1") (pintype "passive"))
      (node (ref "R18") (pin "1") (pinfunction "1_1") (pintype "passive"))
      (node (ref "U1") (pin "14") (pinfunction "PA0(ADC123_IN0/WKUP)_14") (pintype "passive"))
    )
    (net (code "54") (name "/VOLTAGE_2") (class "Default")
      (node (ref "R19") (pin "1") (pinfunction "1_1") (pintype "passive"))
      (node (ref "R20") (pin "1") (pinfunction "1_1") (pintype "passive"))
      (node (ref "U1") (pin "15") (pinfunction "PA1(ADC123_IN1)_15") (pintype "passive"))
    )
    (net (code "55") (name "/VOLTAGE_3") (class "Default")
      (node (ref "R21") (pin "1") (pinfunction "1_1") (pintype "passive"))
      (node (ref "R22") (pin "1") (pinfunction "1_1") (pintype "passive"))
      (node (ref "U1") (pin "16") (pinfunction "PA2(ADC123_IN2)_16") (pintype "passive"))
    )
    (net (code "56") (name "GND") (class "Default")
      (node (ref "C1") (pin "1") (pinfunction "1_1") (pintype "passive"))
      (node (ref "C10") (pin "2") (pinfunction "2_2") (pintype "passive"))
      (node (ref "C11") (pin "2") (pinfunction "2_2") (pintype "passive"))
      (node (ref "C12") (pin "2") (pinfunction "2_2") (pintype "passive"))
      (node (ref "C13") (pin "1") (pinfunction "1_1") (pintype "passive"))
      (node (ref "C14") (pin "1") (pinfunction "1_1") (pintype "passive"))
      (node (ref "C15") (pin "1") (pinfunction "1_1") (pintype "passive"))
      (node (ref "C16") (pin "2") (pinfunction "2_2") (pintype "passive"))
      (node (ref "C17") (pin "1") (pinfunction "1_1") (pintype "passive"))
      (node (ref "C18") (pin "2") (pinfunction "2_2") (pintype "passive"))
      (node (ref "C2") (pin "1") (pinfunction "1_1") (pintype "passive"))
      (node (ref "C20") (pin "1") (pinfunction "1_1") (pintype "passive"))
      (node (ref "C21") (pin "2") (pinfunction "2_2") (pintype "passive"))
      (node (ref "C22") (pin "1") (pinfunction "1_1") (pintype "passive"))
      (node (ref "C26") (pin "1") (pinfunction "1_1") (pintype "passive"))
      (node (ref "C27") (pin "1") (pinfunction "1_1") (pintype "passive"))
      (node (ref "C29") (pin "2") (pinfunction "2_2") (pintype "passive"))
      (node (ref "C3") (pin "1") (pinfunction "1_1") (pintype "passive"))
      (node (ref "C30") (pin "2") (pinfunction "2_2") (pintype "passive"))
      (node (ref "C31") (pin "1") (pinfunction "1_1") (pintype "passive"))
      (node (ref "C32") (pin "2") (pinfunction "2_2") (pintype "passive"))
      (node (ref "C33") (pin "2") (pinfunction "2_2") (pintype "passive"))
      (node (ref "C34") (pin "2") (pinfunction "2_2") (pintype "passive"))
      (node (ref "C35") (pin "1") (pinfunction "1_1") (pintype "passive"))
      (node (ref "C36") (pin "2") (pinfunction "2_2") (pintype "passive"))
      (node (ref "C37") (pin "1") (pinfunction "1_1") (pintype "passive"))
      (node (ref "C38") (pin "1") (pinfunction "1_1") (pintype "passive"))
      (node (ref "C39") (pin "1") (pinfunction "1_1") (pintype "passive"))
      (node (ref "C4") (pin "1") (pinfunction "1_1") (pintype "passive"))
      (node (ref "C40") (pin "1") (pinfunction "1_1") (pintype "passive"))
      (node (ref "C41") (pin "1") (pinfunction "1_1") (pintype "passive"))
      (node (ref "C42") (pin "1") (pinfunction "1_1") (pintype "passive"))
      (node (ref "C43") (pin "1") (pinfunction "1_1") (pintype "passive"))
      (node (ref "C44") (pin "1") (pinfunction "1_1") (pintype "passive"))
      (node (ref "C45") (pin "2") (pinfunction "2_2") (pintype "passive"))
      (node (ref "C46") (pin "2") (pinfunction "2_2") (pintype "passive"))
      (node (ref "C47") (pin "2") (pinfunction "2_2") (pintype "passive"))
      (node (ref "C5") (pin "1") (pinfunction "1_1") (pintype "passive"))
      (node (ref "C58") (pin "1") (pinfunction "1_1") (pintype "passive"))
      (node (ref "C6") (pin "1") (pinfunction "1_1") (pintype "passive"))
      (node (ref "C64") (pin "1") (pinfunction "1_1") (pintype "passive"))
      (node (ref "C7") (pin "1") (pinfunction "1_1") (pintype "passive"))
      (node (ref "C8") (pin "1") (pinfunction "1_1") (pintype "passive"))
      (node (ref "C9") (pin "2") (pinfunction "2_2") (pintype "passive"))
      (node (ref "D4") (pin "1") (pinfunction "A_1") (pintype "passive"))
      (node (ref "D5") (pin "2") (pinfunction "A_2") (pintype "passive"))
      (node (ref "GND") (pin "1") (pinfunction "1_1") (pintype "passive"))
      (node (ref "P1") (pin "1") (pinfunction "SHELL_1") (pintype "passive"))
      (node (ref "P1") (pin "2") (pinfunction "SHELL_2") (pintype "passive"))
      (node (ref "P1") (pin "3") (pinfunction "SHELL_3") (pintype "passive"))
      (node (ref "P1") (pin "4") (pinfunction "SHELL_4") (pintype "passive"))
      (node (ref "P1") (pin "A1B12") (pinfunction "GND_A1B12") (pintype "passive"))
      (node (ref "P1") (pin "B1A12") (pinfunction "GND_B1A12") (pintype "passive"))
      (node (ref "P12") (pin "1") (pinfunction "15_1") (pintype "passive"))
      (node (ref "P2") (pin "1") (pinfunction "1_1") (pintype "passive"))
      (node (ref "P4") (pin "1") (pinfunction "1_1") (pintype "passive"))
      (node (ref "P5") (pin "3") (pinfunction "3_3") (pintype "passive"))
      (node (ref "P6") (pin "1") (pinfunction "1_1") (pintype "passive"))
      (node (ref "P7") (pin "3") (pinfunction "3_3") (pintype "passive"))
      (node (ref "Q2") (pin "2") (pinfunction "S_2") (pintype "passive"))
      (node (ref "Q4") (pin "2") (pinfunction "S_2") (pintype "passive"))
      (node (ref "Q6") (pin "2") (pinfunction "S_2") (pintype "passive"))
      (node (ref "R10") (pin "2") (pinfunction "2_2") (pintype "passive"))
      (node (ref "R13") (pin "1") (pinfunction "1_1") (pintype "passive"))
      (node (ref "R14") (pin "2") (pinfunction "2_2") (pintype "passive"))
      (node (ref "R16") (pin "2") (pinfunction "2_2") (pintype "passive"))
      (node (ref "R18") (pin "2") (pinfunction "2_2") (pintype "passive"))
      (node (ref "R20") (pin "2") (pinfunction "2_2") (pintype "passive"))
      (node (ref "R22") (pin "2") (pinfunction "2_2") (pintype "passive"))
      (node (ref "R28") (pin "2") (pinfunction "2_2") (pintype "passive"))
      (node (ref "R7") (pin "1") (pinfunction "1_1") (pintype "passive"))
      (node (ref "R8") (pin "1") (pinfunction "1_1") (pintype "passive"))
      (node (ref "R9") (pin "1") (pinfunction "1_1") (pintype "passive"))
      (node (ref "U1") (pin "12") (pinfunction "VSSA_12") (pintype "passive"))
      (node (ref "U1") (pin "18") (pinfunction "VSS_18") (pintype "passive"))
      (node (ref "U1") (pin "60") (pinfunction "BOOT0(VPP)_60") (pintype "passive"))
      (node (ref "U1") (pin "63") (pinfunction "VSS_63") (pintype "passive"))
      (node (ref "U3") (pin "28") (pinfunction "AGND_28") (pintype "passive"))
      (node (ref "U3") (pin "30") (pinfunction "SP2_30") (pintype "passive"))
      (node (ref "U3") (pin "31") (pinfunction "SN2_31") (pintype "passive"))
      (node (ref "U3") (pin "32") (pinfunction "SP1_32") (pintype "passive"))
      (node (ref "U3") (pin "33") (pinfunction "SN1_33") (pintype "passive"))
      (node (ref "U3") (pin "34") (pinfunction "SL_C_34") (pintype "passive"))
      (node (ref "U3") (pin "39") (pinfunction "SL_B_39") (pintype "passive"))
      (node (ref "U3") (pin "44") (pinfunction "SL_A_44") (pintype "passive"))
      (node (ref "U3") (pin "57") (pinfunction "GND(POWER_PAD)_57") (pintype "passive"))
      (node (ref "U4") (pin "2") (pinfunction "GND_2") (pintype "passive"))
      (node (ref "U4") (pin "8") (pinfunction "RS_8") (pintype "input"))
      (node (ref "U5") (pin "4") (pinfunction "GND_4") (pintype "passive"))
      (node (ref "U5") (pin "7") (pinfunction "REF1_7") (pintype "passive"))
      (node (ref "U6") (pin "4") (pinfunction "GND_4") (pintype "passive"))
      (node (ref "U6") (pin "7") (pinfunction "REF1_7") (pintype "passive"))
      (node (ref "U7") (pin "4") (pinfunction "GND_4") (pintype "passive"))
      (node (ref "U7") (pin "7") (pinfunction "REF1_7") (pintype "passive"))
      (node (ref "U8") (pin "1") (pinfunction "GND_1") (pintype "passive"))
    )
    (net (code "57") (name "Net-(C16-Pad1)") (class "Default")
      (node (ref "C16") (pin "1") (pinfunction "1_1") (pintype "passive"))
      (node (ref "R12") (pin "2") (pinfunction "2_2") (pintype "passive"))
    )
    (net (code "58") (name "Net-(D1-PadK)") (class "Default")
      (node (ref "D1") (pin "K") (pinfunction "K_K") (pintype "passive"))
      (node (ref "R7") (pin "2") (pinfunction "2_2") (pintype "passive"))
    )
    (net (code "59") (name "Net-(D2-PadK)") (class "Default")
      (node (ref "D2") (pin "K") (pinfunction "K_K") (pintype "passive"))
      (node (ref "R8") (pin "2") (pinfunction "2_2") (pintype "passive"))
    )
    (net (code "60") (name "Net-(D3-PadK)") (class "Default")
      (node (ref "D3") (pin "K") (pinfunction "K_K") (pintype "passive"))
      (node (ref "R9") (pin "2") (pinfunction "2_2") (pintype "passive"))
    )
    (net (code "61") (name "Net-(D4-K)") (class "Default")
      (node (ref "C28") (pin "1") (pinfunction "1_1") (pintype "passive"))
      (node (ref "D4") (pin "2") (pinfunction "K_2") (pintype "passive"))
      (node (ref "L2") (pin "1") (pinfunction "Pri-_1") (pintype "passive"))
      (node (ref "U3") (pin "50") (pinfunction "PH_50") (pintype "passive"))
      (node (ref "U3") (pin "51") (pinfunction "PH_51") (pintype "passive"))
    )
    (net (code "62") (name "Net-(P1-DN1)") (class "Default")
      (node (ref "P1") (pin "A7") (pinfunction "DN1_A7") (pintype "passive"))
      (node (ref "P1") (pin "B7") (pinfunction "DN2_B7") (pintype "passive"))
      (node (ref "R3") (pin "2") (pinfunction "2_2") (pintype "passive"))
    )
    (net (code "63") (name "Net-(P1-DP1)") (class "Default")
      (node (ref "P1") (pin "A6") (pinfunction "DP1_A6") (pintype "passive"))
      (node (ref "P1") (pin "B6") (pinfunction "DP2_B6") (pintype "passive"))
      (node (ref "R2") (pin "2") (pinfunction "2_2") (pintype "passive"))
    )
    (net (code "64") (name "Net-(P1-VBUS-PadA4B9)") (class "Default")
      (node (ref "P1") (pin "A4B9") (pinfunction "VBUS_A4B9") (pintype "passive"))
      (node (ref "P1") (pin "B4A9") (pinfunction "VBUS_B4A9") (pintype "passive"))
      (node (ref "R1") (pin "2") (pinfunction "2_2") (pintype "passive"))
    )
    (net (code "65") (name "Net-(P4-Pad6)") (class "Default")
      (node (ref "P4") (pin "6") (pinfunction "6_6") (pintype "passive"))
      (node (ref "R42") (pin "1") (pinfunction "1_1") (pintype "passive"))
      (node (ref "R43") (pin "1") (pinfunction "1_1") (pintype "passive"))
      (node (ref "R44") (pin "1") (pinfunction "1_1") (pintype "passive"))
      (node (ref "U11") (pin "2") (pinfunction "2_2") (pintype "passive"))
    )
    (net (code "66") (name "Net-(P6-Pad3)") (class "Default")
      (node (ref "P6") (pin "3") (pinfunction "3_3") (pintype "passive"))
      (node (ref "R6") (pin "2") (pinfunction "2_2") (pintype "passive"))
    )
    (net (code "67") (name "Net-(Q1-G)") (class "Default")
      (node (ref "Q1") (pin "1") (pinfunction "G_1") (pintype "passive"))
      (node (ref "R25") (pin "2") (pinfunction "2_2") (pintype "passive"))
    )
    (net (code "68") (name "Net-(Q2-G)") (class "Default")
      (node (ref "Q2") (pin "1") (pinfunction "G_1") (pintype "passive"))
      (node (ref "R26") (pin "2") (pinfunction "2_2") (pintype "passive"))
    )
    (net (code "69") (name "Net-(Q3-G)") (class "Default")
      (node (ref "Q3") (pin "1") (pinfunction "G_1") (pintype "passive"))
      (node (ref "R30") (pin "2") (pinfunction "2_2") (pintype "passive"))
    )
    (net (code "70") (name "Net-(Q4-G)") (class "Default")
      (node (ref "Q4") (pin "1") (pinfunction "G_1") (pintype "passive"))
      (node (ref "R31") (pin "2") (pinfunction "2_2") (pintype "passive"))
    )
    (net (code "71") (name "Net-(Q5-G)") (class "Default")
      (node (ref "Q5") (pin "1") (pinfunction "G_1") (pintype "passive"))
      (node (ref "R33") (pin "2") (pinfunction "2_2") (pintype "passive"))
    )
    (net (code "72") (name "Net-(Q6-G)") (class "Default")
      (node (ref "Q6") (pin "1") (pinfunction "G_1") (pintype "passive"))
      (node (ref "R34") (pin "2") (pinfunction "2_2") (pintype "passive"))
    )
    (net (code "73") (name "Net-(U1-PH0_OSC_IN)") (class "Default")
      (node (ref "C2") (pin "2") (pinfunction "2_2") (pintype "passive"))
      (node (ref "U1") (pin "5") (pinfunction "PH0_OSC_IN_5") (pintype "passive"))
      (node (ref "X1") (pin "1") (pinfunction "1_1") (pintype "passive"))
    )
    (net (code "74") (name "Net-(U1-PH0_OSC_OUT)") (class "Default")
      (node (ref "C8") (pin "2") (pinfunction "2_2") (pintype "passive"))
      (node (ref "U1") (pin "6") (pinfunction "PH0_OSC_OUT_6") (pintype "passive"))
      (node (ref "X1") (pin "2") (pinfunction "2_2") (pintype "passive"))
    )
    (net (code "75") (name "Net-(U1-VCAP1)") (class "Default")
      (node (ref "C3") (pin "2") (pinfunction "2_2") (pintype "passive"))
      (node (ref "U1") (pin "31") (pinfunction "VCAP1_31") (pintype "passive"))
    )
    (net (code "76") (name "Net-(U1-VCAP2)") (class "Default")
      (node (ref "C4") (pin "2") (pinfunction "2_2") (pintype "passive"))
      (node (ref "U1") (pin "47") (pinfunction "VCAP2_47") (pintype "passive"))
    )
    (net (code "77") (name "Net-(U3-AVDD)") (class "Default")
      (node (ref "C20") (pin "2") (pinfunction "2_2") (pintype "passive"))
      (node (ref "U3") (pin "24") (pinfunction "REF_24") (pintype "passive"))
      (node (ref "U3") (pin "27") (pinfunction "AVDD_27") (pintype "passive"))
    )
    (net (code "78") (name "Net-(U3-BST_A)") (class "Default")
      (node (ref "C23") (pin "2") (pinfunction "2_2") (pintype "passive"))
      (node (ref "U3") (pin "48") (pinfunction "BST_A_48") (pintype "passive"))
    )
    (net (code "79") (name "Net-(U3-BST_B)") (class "Default")
      (node (ref "C24") (pin "2") (pinfunction "2_2") (pintype "passive"))
      (node (ref "U3") (pin "43") (pinfunction "BST_B_43") (pintype "passive"))
    )
    (net (code "80") (name "Net-(U3-BST_BK)") (class "Default")
      (node (ref "C28") (pin "2") (pinfunction "2_2") (pintype "passive"))
      (node (ref "U3") (pin "52") (pinfunction "BST_BK_52") (pintype "passive"))
    )
    (net (code "81") (name "Net-(U3-BST_C)") (class "Default")
      (node (ref "C25") (pin "2") (pinfunction "2_2") (pintype "passive"))
      (node (ref "U3") (pin "38") (pinfunction "BST_C_38") (pintype "passive"))
    )
    (net (code "82") (name "Net-(U3-COMP)") (class "Default")
      (node (ref "C18") (pin "1") (pinfunction "1_1") (pintype "passive"))
      (node (ref "R12") (pin "1") (pinfunction "1_1") (pintype "passive"))
      (node (ref "U3") (pin "2") (pinfunction "COMP_2") (pintype "passive"))
    )
    (net (code "83") (name "Net-(U3-CP1)") (class "Default")
      (node (ref "C19") (pin "1") (pinfunction "1_1") (pintype "passive"))
      (node (ref "U3") (pin "14") (pinfunction "CP1_14") (pintype "passive"))
    )
    (net (code "84") (name "Net-(U3-CP2)") (class "Default")
      (node (ref "C19") (pin "2") (pinfunction "2_2") (pintype "passive"))
      (node (ref "U3") (pin "15") (pinfunction "CP2_15") (pintype "passive"))
    )
    (net (code "85") (name "Net-(U3-DTC)") (class "Default")
      (node (ref "R13") (pin "2") (pinfunction "2_2") (pintype "passive"))
      (node (ref "U3") (pin "7") (pinfunction "DTC_7") (pintype "passive"))
    )
    (net (code "86") (name "Net-(U3-DVDD)") (class "Default")
      (node (ref "C17") (pin "2") (pinfunction "2_2") (pintype "passive"))
      (node (ref "U3") (pin "23") (pinfunction "DVDD_23") (pintype "passive"))
    )
    (net (code "87") (name "Net-(U3-GVDD)") (class "Default")
      (node (ref "C14") (pin "2") (pinfunction "2_2") (pintype "passive"))
      (node (ref "C15") (pin "2") (pinfunction "2_2") (pintype "passive"))
      (node (ref "U3") (pin "13") (pinfunction "GVDD_13") (pintype "passive"))
    )
    (net (code "88") (name "Net-(U3-RT_CLK)") (class "Default")
      (node (ref "R14") (pin "1") (pinfunction "1_1") (pintype "passive"))
      (node (ref "U3") (pin "1") (pinfunction "RT_CLK_1") (pintype "passive"))
    )
    (net (code "89") (name "Net-(U3-SS_TR)") (class "Default")
      (node (ref "C22") (pin "2") (pinfunction "2_2") (pintype "passive"))
      (node (ref "U3") (pin "56") (pinfunction "SS_TR_56") (pintype "passive"))
    )
    (net (code "90") (name "Net-(U3-VSENSE)") (class "Default")
      (node (ref "R10") (pin "1") (pinfunction "1_1") (pintype "passive"))
      (node (ref "R11") (pin "2") (pinfunction "2_2") (pintype "passive"))
      (node (ref "U3") (pin "3") (pinfunction "VSENSE_3") (pintype "passive"))
    )
    (net (code "91") (name "Net-(U5-OUT)") (class "Default")
      (node (ref "R35") (pin "2") (pinfunction "2_2") (pintype "passive"))
      (node (ref "U5") (pin "8") (pinfunction "OUT_8") (pintype "passive"))
    )
    (net (code "92") (name "Net-(U6-OUT)") (class "Default")
      (node (ref "R36") (pin "2") (pinfunction "2_2") (pintype "passive"))
      (node (ref "U6") (pin "8") (pinfunction "OUT_8") (pintype "passive"))
    )
    (net (code "93") (name "Net-(U7-OUT)") (class "Default")
      (node (ref "R37") (pin "2") (pinfunction "2_2") (pintype "passive"))
      (node (ref "U7") (pin "8") (pinfunction "OUT_8") (pintype "passive"))
    )
    (net (code "94") (name "VCC") (class "Default")
      (node (ref "C10") (pin "1") (pinfunction "1_1") (pintype "passive"))
      (node (ref "C11") (pin "1") (pinfunction "1_1") (pintype "passive"))
      (node (ref "C12") (pin "1") (pinfunction "1_1") (pintype "passive"))
      (node (ref "C21") (pin "1") (pinfunction "1_1") (pintype "passive"))
      (node (ref "C34") (pin "1") (pinfunction "1_1") (pintype "passive"))
      (node (ref "C35") (pin "2") (pinfunction "2_2") (pintype "passive"))
      (node (ref "C38") (pin "2") (pinfunction "2_2") (pintype "passive"))
      (node (ref "C42") (pin "2") (pinfunction "2_2") (pintype "passive"))
      (node (ref "C5") (pin "2") (pinfunction "2_2") (pintype "passive"))
      (node (ref "C6") (pin "2") (pinfunction "2_2") (pintype "passive"))
      (node (ref "C64") (pin "2") (pinfunction "2_2") (pintype "passive"))
      (node (ref "C9") (pin "1") (pinfunction "1_1") (pintype "passive"))
      (node (ref "D1") (pin "A") (pinfunction "A_A") (pintype "passive"))
      (node (ref "P5") (pin "2") (pinfunction "2_2") (pintype "passive"))
      (node (ref "P7") (pin "5") (pinfunction "5_5") (pintype "passive"))
      (node (ref "R27") (pin "2") (pinfunction "2_2") (pintype "passive"))
      (node (ref "R39") (pin "1") (pinfunction "1_1") (pintype "passive"))
      (node (ref "U1") (pin "1") (pinfunction "VBAT_1") (pintype "passive"))
      (node (ref "U1") (pin "13") (pinfunction "VDDA_13") (pintype "passive"))
      (node (ref "U1") (pin "19") (pinfunction "VDD_19") (pintype "passive"))
      (node (ref "U1") (pin "32") (pinfunction "VDD_32") (pintype "passive"))
      (node (ref "U1") (pin "48") (pinfunction "VDD_48") (pintype "passive"))
      (node (ref "U1") (pin "64") (pinfunction "VDD_64") (pintype "passive"))
      (node (ref "U11") (pin "1") (pinfunction "1_1") (pintype "passive"))
      (node (ref "U3") (pin "49") (pinfunction "VDD_SPI_49") (pintype "passive"))
      (node (ref "U4") (pin "5") (pinfunction "Vref_5") (pintype "output"))
      (node (ref "U5") (pin "5") (pinfunction "VS_5") (pintype "passive"))
      (node (ref "U5") (pin "6") (pinfunction "REF2_6") (pintype "passive"))
      (node (ref "U6") (pin "5") (pinfunction "VS_5") (pintype "passive"))
      (node (ref "U6") (pin "6") (pinfunction "REF2_6") (pintype "passive"))
      (node (ref "U7") (pin "5") (pinfunction "VS_5") (pintype "passive"))
      (node (ref "U7") (pin "6") (pinfunction "REF2_6") (pintype "passive"))
      (node (ref "U8") (pin "2") (pinfunction "Vout_2") (pintype "passive"))
      (node (ref "VCC") (pin "1") (pinfunction "1_1") (pintype "passive"))
    )
    (net (code "95") (name "unconnected-(P1-CC1-PadA5)") (class "Default")
      (node (ref "P1") (pin "A5") (pinfunction "CC1_A5") (pintype "passive+no_connect"))
    )
    (net (code "96") (name "unconnected-(P1-CC2-PadB5)") (class "Default")
      (node (ref "P1") (pin "B5") (pinfunction "CC2_B5") (pintype "passive+no_connect"))
    )
    (net (code "97") (name "unconnected-(P1-SBU1-PadA8)") (class "Default")
      (node (ref "P1") (pin "A8") (pinfunction "SBU1_A8") (pintype "passive+no_connect"))
    )
    (net (code "98") (name "unconnected-(P1-SBU2-PadB8)") (class "Default")
      (node (ref "P1") (pin "B8") (pinfunction "SBU2_B8") (pintype "passive+no_connect"))
    )
    (net (code "99") (name "unconnected-(U1-PA15(JTD1)-Pad50)") (class "Default")
      (node (ref "U1") (pin "50") (pinfunction "PA15(JTD1)_50") (pintype "passive+no_connect"))
    )
    (net (code "100") (name "unconnected-(U1-PB2{slash}BOOT1-Pad28)") (class "Default")
      (node (ref "U1") (pin "28") (pinfunction "PB2/BOOT1_28") (pintype "passive+no_connect"))
    )
    (net (code "101") (name "unconnected-(U1-PB3(JTDO{slash}TRACESWO)-Pad55)") (class "Default")
      (node (ref "U1") (pin "55") (pinfunction "PB3(JTDO/TRACESWO)_55") (pintype "passive+no_connect"))
    )
    (net (code "102") (name "unconnected-(U1-PB4(NJRST)-Pad56)") (class "Default")
      (node (ref "U1") (pin "56") (pinfunction "PB4(NJRST)_56") (pintype "passive+no_connect"))
    )
    (net (code "103") (name "unconnected-(U1-PB12-Pad33)") (class "Default")
      (node (ref "U1") (pin "33") (pinfunction "PB12_33") (pintype "passive+no_connect"))
    )
    (net (code "104") (name "unconnected-(U1-PC13-Pad2)") (class "Default")
      (node (ref "U1") (pin "2") (pinfunction "PC13_2") (pintype "passive+no_connect"))
    )
    (net (code "105") (name "unconnected-(U1-PC14{slash}OSC32_IN-Pad3)") (class "Default")
      (node (ref "U1") (pin "3") (pinfunction "PC14/OSC32_IN_3") (pintype "passive+no_connect"))
    )
    (net (code "106") (name "unconnected-(U1-PC15{slash}OSC32_OUT-Pad4)") (class "Default")
      (node (ref "U1") (pin "4") (pinfunction "PC15/OSC32_OUT_4") (pintype "passive+no_connect"))
    )
    (net (code "107") (name "unconnected-(U1-PD2-Pad54)") (class "Default")
      (node (ref "U1") (pin "54") (pinfunction "PD2_54") (pintype "passive+no_connect"))
    )
    (net (code "108") (name "unconnected-(U3-DC_CAL-Pad12)") (class "Default")
      (node (ref "U3") (pin "12") (pinfunction "DC_CAL_12") (pintype "passive+no_connect"))
    )
    (net (code "109") (name "unconnected-(U3-EN_BUCK-Pad55)") (class "Default")
      (node (ref "U3") (pin "55") (pinfunction "EN_BUCK_55") (pintype "passive+no_connect"))
    )
    (net (code "110") (name "unconnected-(U3-OCTW-Pad5)") (class "Default")
      (node (ref "U3") (pin "5") (pinfunction "OCTW_5") (pintype "passive+no_connect"))
    )
    (net (code "111") (name "unconnected-(U3-PWRGD-Pad4)") (class "Default")
      (node (ref "U3") (pin "4") (pinfunction "PWRGD_4") (pintype "passive+no_connect"))
    )
    (net (code "112") (name "unconnected-(U3-SO1-Pad25)") (class "Default")
      (node (ref "U3") (pin "25") (pinfunction "SO1_25") (pintype "passive+no_connect"))
    )
    (net (code "113") (name "unconnected-(U3-SO2-Pad26)") (class "Default")
      (node (ref "U3") (pin "26") (pinfunction "SO2_26") (pintype "passive+no_connect"))
    )
    (net (code "114") (name "unconnected-(U5-NC-Pad1)") (class "Default")
      (node (ref "U5") (pin "1") (pinfunction "NC_1") (pintype "passive+no_connect"))
    )
    (net (code "115") (name "unconnected-(U6-NC-Pad1)") (class "Default")
      (node (ref "U6") (pin "1") (pinfunction "NC_1") (pintype "passive+no_connect"))
    )
    (net (code "116") (name "unconnected-(U7-NC-Pad1)") (class "Default")
      (node (ref "U7") (pin "1") (pinfunction "NC_1") (pintype "passive+no_connect"))
    )
  )
)
